# oysm_Keyboard_Buttons.net
KiCad netlist of a schematic drawn in Altium Designer
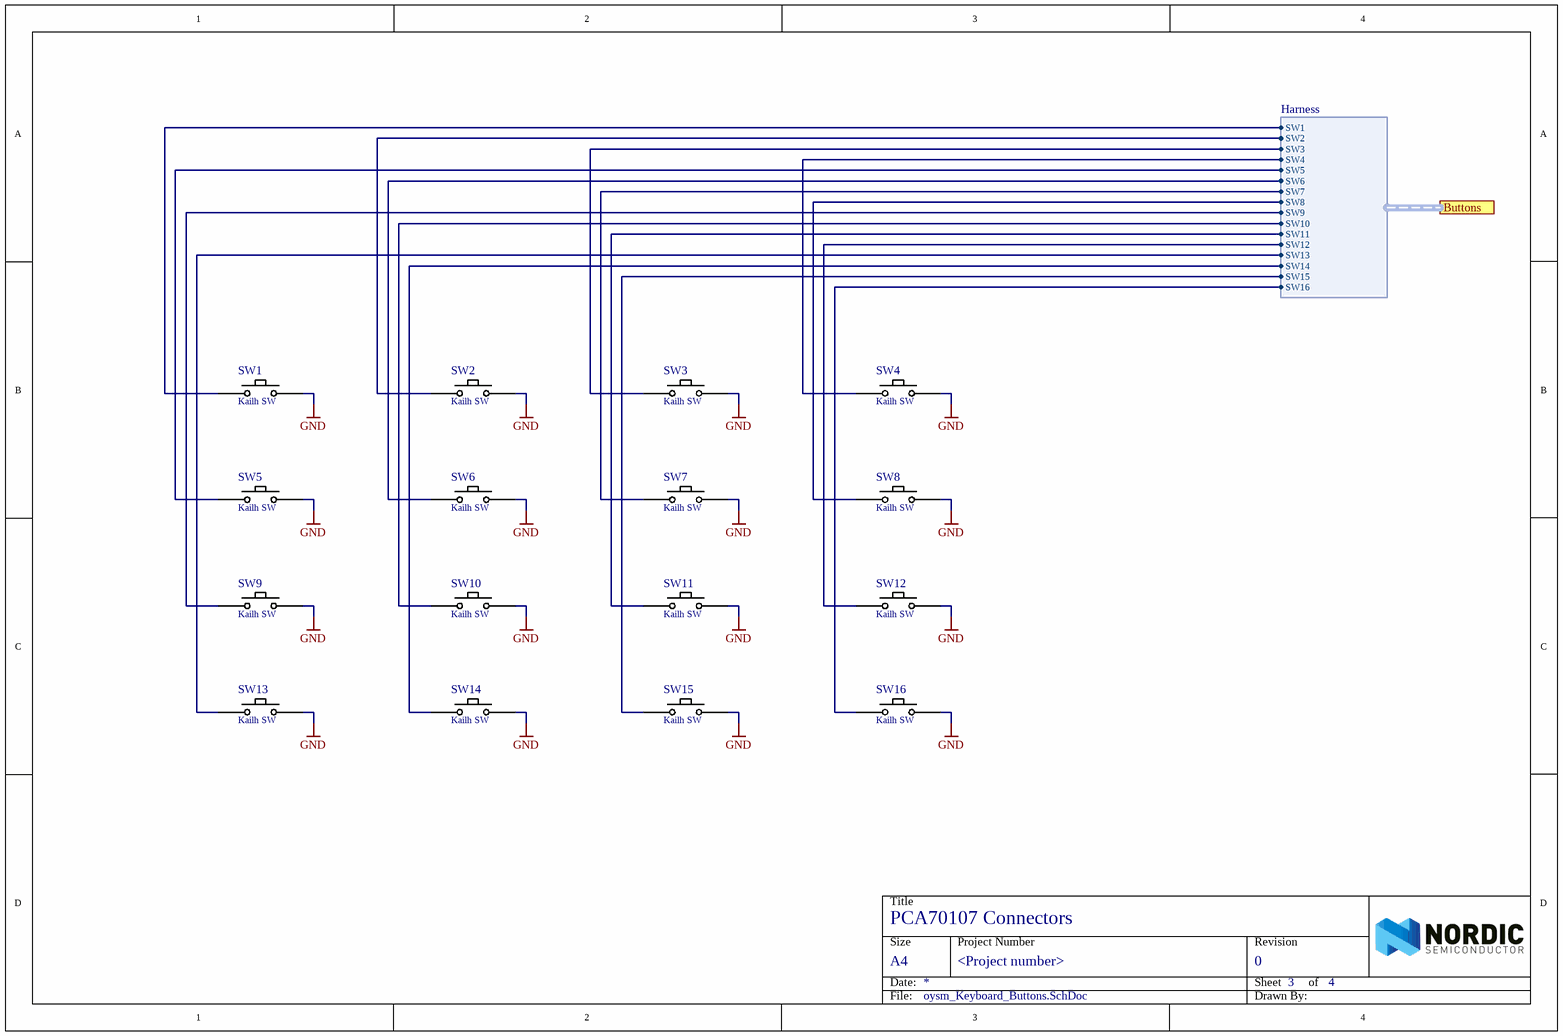
[diagram p0: oysm_Keyboard_Buttons.SchDoc]

(export (version "E")
  (design (tool "Eeschema 10.0.6"))
  (components
    (comp (ref "SW1")
      (value "Kailh SW")
      (footprint "Kailh_Mechanical_Key")
      (description "Kailh Mechanical keyboard switch")
      (libsource (lib "OVLib_64") (part "Pushbutton_2P"))
    )
    (comp (ref "SW2")
      (value "Kailh SW")
      (footprint "Kailh_Mechanical_Key")
      (description "Kailh Mechanical keyboard switch")
      (libsource (lib "OVLib_64") (part "Pushbutton_2P"))
    )
    (comp (ref "SW3")
      (value "Kailh SW")
      (footprint "Kailh_Mechanical_Key")
      (description "Kailh Mechanical keyboard switch")
      (libsource (lib "OVLib_64") (part "Pushbutton_2P"))
    )
    (comp (ref "SW4")
      (value "Kailh SW")
      (footprint "Kailh_Mechanical_Key")
      (description "Kailh Mechanical keyboard switch")
      (libsource (lib "OVLib_64") (part "Pushbutton_2P"))
    )
    (comp (ref "SW5")
      (value "Kailh SW")
      (footprint "Kailh_Mechanical_Key")
      (description "Kailh Mechanical keyboard switch")
      (libsource (lib "OVLib_64") (part "Pushbutton_2P"))
    )
    (comp (ref "SW6")
      (value "Kailh SW")
      (footprint "Kailh_Mechanical_Key")
      (description "Kailh Mechanical keyboard switch")
      (libsource (lib "OVLib_64") (part "Pushbutton_2P"))
    )
    (comp (ref "SW7")
      (value "Kailh SW")
      (footprint "Kailh_Mechanical_Key")
      (description "Kailh Mechanical keyboard switch")
      (libsource (lib "OVLib_64") (part "Pushbutton_2P"))
    )
    (comp (ref "SW8")
      (value "Kailh SW")
      (footprint "Kailh_Mechanical_Key")
      (description "Kailh Mechanical keyboard switch")
      (libsource (lib "OVLib_64") (part "Pushbutton_2P"))
    )
    (comp (ref "SW9")
      (value "Kailh SW")
      (footprint "Kailh_Mechanical_Key")
      (description "Kailh Mechanical keyboard switch")
      (libsource (lib "OVLib_64") (part "Pushbutton_2P"))
    )
    (comp (ref "SW10")
      (value "Kailh SW")
      (footprint "Kailh_Mechanical_Key")
      (description "Kailh Mechanical keyboard switch")
      (libsource (lib "OVLib_64") (part "Pushbutton_2P"))
    )
    (comp (ref "SW11")
      (value "Kailh SW")
      (footprint "Kailh_Mechanical_Key")
      (description "Kailh Mechanical keyboard switch")
      (libsource (lib "OVLib_64") (part "Pushbutton_2P"))
    )
    (comp (ref "SW12")
      (value "Kailh SW")
      (footprint "Kailh_Mechanical_Key")
      (description "Kailh Mechanical keyboard switch")
      (libsource (lib "OVLib_64") (part "Pushbutton_2P"))
    )
    (comp (ref "SW13")
      (value "Kailh SW")
      (footprint "Kailh_Mechanical_Key")
      (description "Kailh Mechanical keyboard switch")
      (libsource (lib "OVLib_64") (part "Pushbutton_2P"))
    )
    (comp (ref "SW14")
      (value "Kailh SW")
      (footprint "Kailh_Mechanical_Key")
      (description "Kailh Mechanical keyboard switch")
      (libsource (lib "OVLib_64") (part "Pushbutton_2P"))
    )
    (comp (ref "SW15")
      (value "Kailh SW")
      (footprint "Kailh_Mechanical_Key")
      (description "Kailh Mechanical keyboard switch")
      (libsource (lib "OVLib_64") (part "Pushbutton_2P"))
    )
    (comp (ref "SW16")
      (value "Kailh SW")
      (footprint "Kailh_Mechanical_Key")
      (description "Kailh Mechanical keyboard switch")
      (libsource (lib "OVLib_64") (part "Pushbutton_2P"))
    )
  )
  (nets
    (net (code "2") (name "/SW1") (class "Default")
      (node (ref "SW1") (pin "1") (pinfunction "1_1") (pintype "passive"))
    )
    (net (code "3") (name "/SW2") (class "Default")
      (node (ref "SW2") (pin "1") (pinfunction "1_1") (pintype "passive"))
    )
    (net (code "4") (name "/SW3") (class "Default")
      (node (ref "SW3") (pin "1") (pinfunction "1_1") (pintype "passive"))
    )
    (net (code "5") (name "/SW4") (class "Default")
      (node (ref "SW4") (pin "1") (pinfunction "1_1") (pintype "passive"))
    )
    (net (code "6") (name "/SW5") (class "Default")
      (node (ref "SW5") (pin "1") (pinfunction "1_1") (pintype "passive"))
    )
    (net (code "7") (name "/SW6") (class "Default")
      (node (ref "SW6") (pin "1") (pinfunction "1_1") (pintype "passive"))
    )
    (net (code "8") (name "/SW7") (class "Default")
      (node (ref "SW7") (pin "1") (pinfunction "1_1") (pintype "passive"))
    )
    (net (code "9") (name "/SW8") (class "Default")
      (node (ref "SW8") (pin "1") (pinfunction "1_1") (pintype "passive"))
    )
    (net (code "10") (name "/SW9") (class "Default")
      (node (ref "SW9") (pin "1") (pinfunction "1_1") (pintype "passive"))
    )
    (net (code "11") (name "/SW10") (class "Default")
      (node (ref "SW10") (pin "1") (pinfunction "1_1") (pintype "passive"))
    )
    (net (code "12") (name "/SW11") (class "Default")
      (node (ref "SW11") (pin "1") (pinfunction "1_1") (pintype "passive"))
    )
    (net (code "13") (name "/SW12") (class "Default")
      (node (ref "SW12") (pin "1") (pinfunction "1_1") (pintype "passive"))
    )
    (net (code "14") (name "/SW13") (class "Default")
      (node (ref "SW13") (pin "1") (pinfunction "1_1") (pintype "passive"))
    )
    (net (code "15") (name "/SW14") (class "Default")
      (node (ref "SW14") (pin "1") (pinfunction "1_1") (pintype "passive"))
    )
    (net (code "16") (name "/SW15") (class "Default")
      (node (ref "SW15") (pin "1") (pinfunction "1_1") (pintype "passive"))
    )
    (net (code "17") (name "/SW16") (class "Default")
      (node (ref "SW16") (pin "1") (pinfunction "1_1") (pintype "passive"))
    )
    (net (code "19") (name "GND") (class "Default")
      (node (ref "SW1") (pin "2") (pinfunction "2_2") (pintype "passive"))
      (node (ref "SW10") (pin "2") (pinfunction "2_2") (pintype "passive"))
      (node (ref "SW11") (pin "2") (pinfunction "2_2") (pintype "passive"))
      (node (ref "SW12") (pin "2") (pinfunction "2_2") (pintype "passive"))
      (node (ref "SW13") (pin "2") (pinfunction "2_2") (pintype "passive"))
      (node (ref "SW14") (pin "2") (pinfunction "2_2") (pintype "passive"))
      (node (ref "SW15") (pin "2") (pinfunction "2_2") (pintype "passive"))
      (node (ref "SW16") (pin "2") (pinfunction "2_2") (pintype "passive"))
      (node (ref "SW2") (pin "2") (pinfunction "2_2") (pintype "passive"))
      (node (ref "SW3") (pin "2") (pinfunction "2_2") (pintype "passive"))
      (node (ref "SW4") (pin "2") (pinfunction "2_2") (pintype "passive"))
      (node (ref "SW5") (pin "2") (pinfunction "2_2") (pintype "passive"))
      (node (ref "SW6") (pin "2") (pinfunction "2_2") (pintype "passive"))
      (node (ref "SW7") (pin "2") (pinfunction "2_2") (pintype "passive"))
      (node (ref "SW8") (pin "2") (pinfunction "2_2") (pintype "passive"))
      (node (ref "SW9") (pin "2") (pinfunction "2_2") (pintype "passive"))
    )
  )
)
